# Var_7_scheme.net
KiCad netlist of a schematic drawn in Altium Designer
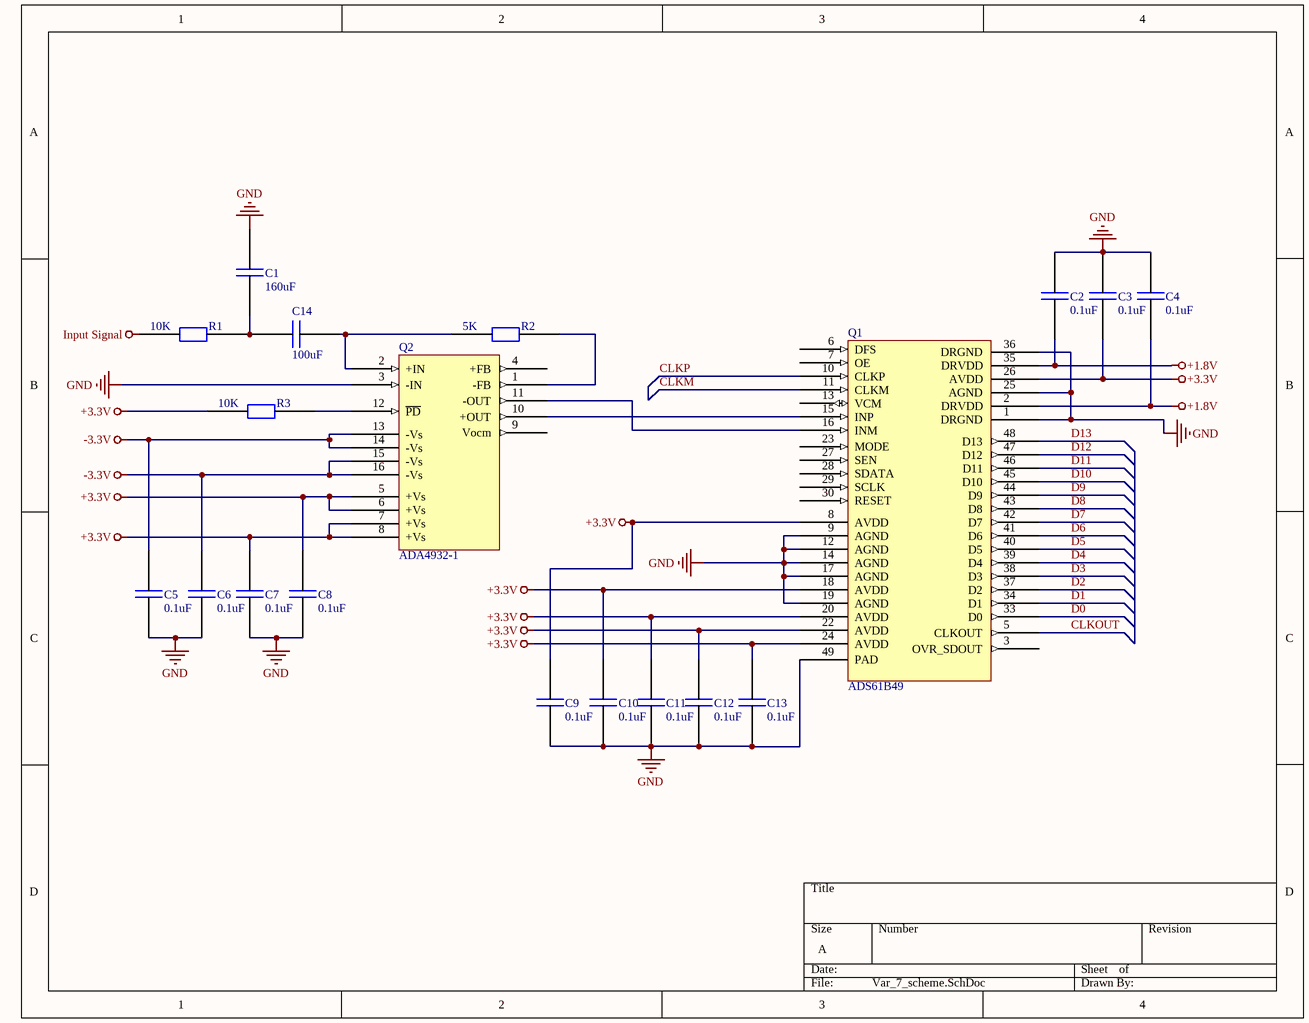
[diagram p0: Var_7_scheme.SchDoc]

(export (version "E")
  (design (tool "Eeschema 10.0.6"))
  (components
    (comp (ref "C1") (value "160uF") (footprint "CAP0603") (libsource (lib "Var_7") (part "Capacitor")))
    (comp (ref "C2") (value "0.1uF") (footprint "CAP0603") (libsource (lib "Var_7") (part "Capacitor")))
    (comp (ref "C3") (value "0.1uF") (footprint "CAP0603") (libsource (lib "Var_7") (part "Capacitor")))
    (comp (ref "C4") (value "0.1uF") (footprint "CAP0603") (libsource (lib "Var_7") (part "Capacitor")))
    (comp (ref "C5") (value "0.1uF") (footprint "CAP0603") (libsource (lib "Var_7") (part "Capacitor")))
    (comp (ref "C6") (value "0.1uF") (footprint "CAP0603") (libsource (lib "Var_7") (part "Capacitor")))
    (comp (ref "C7") (value "0.1uF") (footprint "CAP0603") (libsource (lib "Var_7") (part "Capacitor")))
    (comp (ref "C8") (value "0.1uF") (footprint "CAP0603") (libsource (lib "Var_7") (part "Capacitor")))
    (comp (ref "C9") (value "0.1uF") (footprint "CAP0603") (libsource (lib "Var_7") (part "Capacitor")))
    (comp (ref "C10") (value "0.1uF") (footprint "CAP0603") (libsource (lib "Var_7") (part "Capacitor")))
    (comp (ref "C11") (value "0.1uF") (footprint "CAP0603") (libsource (lib "Var_7") (part "Capacitor")))
    (comp (ref "C12") (value "0.1uF") (footprint "CAP0603") (libsource (lib "Var_7") (part "Capacitor")))
    (comp (ref "C13") (value "0.1uF") (footprint "CAP0603") (libsource (lib "Var_7") (part "Capacitor")))
    (comp (ref "C14") (value "100uF") (footprint "CAP0603") (libsource (lib "Var_7") (part "Capacitor")))
    (comp (ref "Q1") (value "ADS61B49") (footprint "QFN49") (libsource (lib "Var_7") (part "ADS61B49")))
    (comp (ref "Q2") (value "ADA4932-1") (footprint "QFN17") (libsource (lib "Var_7") (part "ADA4932-1")))
    (comp (ref "R1") (value "10K") (footprint "RES0805") (libsource (lib "Var_7") (part "Resistor")))
    (comp (ref "R2") (value "5K") (footprint "RES0805") (libsource (lib "Var_7") (part "Resistor")))
    (comp (ref "R3") (value "10K") (footprint "RES0805") (libsource (lib "Var_7") (part "Resistor")))
  )
  (nets
    (net (code "1") (name "+1.8V") (class "Default")
      (node (ref "C2") (pin "2") (pinfunction "2_2") (pintype "passive"))
      (node (ref "C4") (pin "2") (pinfunction "2_2") (pintype "passive"))
      (node (ref "Q1") (pin "2") (pinfunction "DRVDD_2") (pintype "power_in"))
      (node (ref "Q1") (pin "35") (pinfunction "DRVDD_35") (pintype "power_in"))
    )
    (net (code "2") (name "+3.3V") (class "Default")
      (node (ref "C10") (pin "1") (pinfunction "1_1") (pintype "passive"))
      (node (ref "C11") (pin "1") (pinfunction "1_1") (pintype "passive"))
      (node (ref "C12") (pin "1") (pinfunction "1_1") (pintype "passive"))
      (node (ref "C13") (pin "1") (pinfunction "1_1") (pintype "passive"))
      (node (ref "C3") (pin "2") (pinfunction "2_2") (pintype "passive"))
      (node (ref "C7") (pin "1") (pinfunction "1_1") (pintype "passive"))
      (node (ref "C8") (pin "1") (pinfunction "1_1") (pintype "passive"))
      (node (ref "C9") (pin "1") (pinfunction "1_1") (pintype "passive"))
      (node (ref "Q1") (pin "18") (pinfunction "AVDD_18") (pintype "power_in"))
      (node (ref "Q1") (pin "20") (pinfunction "AVDD_20") (pintype "power_in"))
      (node (ref "Q1") (pin "22") (pinfunction "AVDD_22") (pintype "power_in"))
      (node (ref "Q1") (pin "24") (pinfunction "AVDD_24") (pintype "power_in"))
      (node (ref "Q1") (pin "26") (pinfunction "AVDD_26") (pintype "power_in"))
      (node (ref "Q1") (pin "8") (pinfunction "AVDD_8") (pintype "power_in"))
      (node (ref "Q2") (pin "5") (pinfunction "+Vs_5") (pintype "power_in"))
      (node (ref "Q2") (pin "6") (pinfunction "+Vs_6") (pintype "power_in"))
      (node (ref "Q2") (pin "7") (pinfunction "+Vs_7") (pintype "power_in"))
      (node (ref "Q2") (pin "8") (pinfunction "+Vs_8") (pintype "power_in"))
      (node (ref "R3") (pin "2") (pinfunction "2_2") (pintype "passive"))
    )
    (net (code "3") (name "-3.3V") (class "Default")
      (node (ref "C5") (pin "1") (pinfunction "1_1") (pintype "passive"))
      (node (ref "C6") (pin "1") (pinfunction "1_1") (pintype "passive"))
      (node (ref "Q2") (pin "13") (pinfunction "-Vs_13") (pintype "power_in"))
      (node (ref "Q2") (pin "14") (pinfunction "-Vs_14") (pintype "power_in"))
      (node (ref "Q2") (pin "15") (pinfunction "-Vs_15") (pintype "power_in"))
      (node (ref "Q2") (pin "16") (pinfunction "-Vs_16") (pintype "power_in"))
    )
    (net (code "4") (name "/CLKM") (class "Default")
      (node (ref "Q1") (pin "11") (pinfunction "CLKM_11") (pintype "input"))
    )
    (net (code "5") (name "/CLKOUT") (class "Default")
      (node (ref "Q1") (pin "5") (pinfunction "CLKOUT_5") (pintype "output"))
    )
    (net (code "6") (name "/CLKP") (class "Default")
      (node (ref "Q1") (pin "10") (pinfunction "CLKP_10") (pintype "input"))
    )
    (net (code "7") (name "/D0") (class "Default")
      (node (ref "Q1") (pin "33") (pinfunction "D0_33") (pintype "output"))
    )
    (net (code "8") (name "/D1") (class "Default")
      (node (ref "Q1") (pin "34") (pinfunction "D1_34") (pintype "output"))
    )
    (net (code "9") (name "/D2") (class "Default")
      (node (ref "Q1") (pin "37") (pinfunction "D2_37") (pintype "output"))
    )
    (net (code "10") (name "/D3") (class "Default")
      (node (ref "Q1") (pin "38") (pinfunction "D3_38") (pintype "output"))
    )
    (net (code "11") (name "/D4") (class "Default")
      (node (ref "Q1") (pin "39") (pinfunction "D4_39") (pintype "output"))
    )
    (net (code "12") (name "/D5") (class "Default")
      (node (ref "Q1") (pin "40") (pinfunction "D5_40") (pintype "output"))
    )
    (net (code "13") (name "/D6") (class "Default")
      (node (ref "Q1") (pin "41") (pinfunction "D6_41") (pintype "output"))
    )
    (net (code "14") (name "/D7") (class "Default")
      (node (ref "Q1") (pin "42") (pinfunction "D7_42") (pintype "output"))
    )
    (net (code "15") (name "/D8") (class "Default")
      (node (ref "Q1") (pin "43") (pinfunction "D8_43") (pintype "output"))
    )
    (net (code "16") (name "/D9") (class "Default")
      (node (ref "Q1") (pin "44") (pinfunction "D9_44") (pintype "output"))
    )
    (net (code "17") (name "/D10") (class "Default")
      (node (ref "Q1") (pin "45") (pinfunction "D10_45") (pintype "output"))
    )
    (net (code "18") (name "/D11") (class "Default")
      (node (ref "Q1") (pin "46") (pinfunction "D11_46") (pintype "output"))
    )
    (net (code "19") (name "/D12") (class "Default")
      (node (ref "Q1") (pin "47") (pinfunction "D12_47") (pintype "output"))
    )
    (net (code "20") (name "/D13") (class "Default")
      (node (ref "Q1") (pin "48") (pinfunction "D13_48") (pintype "output"))
    )
    (net (code "21") (name "GND") (class "Default")
      (node (ref "C1") (pin "2") (pinfunction "2_2") (pintype "passive"))
      (node (ref "C10") (pin "2") (pinfunction "2_2") (pintype "passive"))
      (node (ref "C11") (pin "2") (pinfunction "2_2") (pintype "passive"))
      (node (ref "C12") (pin "2") (pinfunction "2_2") (pintype "passive"))
      (node (ref "C13") (pin "2") (pinfunction "2_2") (pintype "passive"))
      (node (ref "C2") (pin "1") (pinfunction "1_1") (pintype "passive"))
      (node (ref "C3") (pin "1") (pinfunction "1_1") (pintype "passive"))
      (node (ref "C4") (pin "1") (pinfunction "1_1") (pintype "passive"))
      (node (ref "C5") (pin "2") (pinfunction "2_2") (pintype "passive"))
      (node (ref "C6") (pin "2") (pinfunction "2_2") (pintype "passive"))
      (node (ref "C7") (pin "2") (pinfunction "2_2") (pintype "passive"))
      (node (ref "C8") (pin "2") (pinfunction "2_2") (pintype "passive"))
      (node (ref "C9") (pin "2") (pinfunction "2_2") (pintype "passive"))
      (node (ref "Q1") (pin "1") (pinfunction "DRGND_1") (pintype "power_in"))
      (node (ref "Q1") (pin "12") (pinfunction "AGND_12") (pintype "power_in"))
      (node (ref "Q1") (pin "14") (pinfunction "AGND_14") (pintype "power_in"))
      (node (ref "Q1") (pin "17") (pinfunction "AGND_17") (pintype "power_in"))
      (node (ref "Q1") (pin "19") (pinfunction "AGND_19") (pintype "power_in"))
      (node (ref "Q1") (pin "25") (pinfunction "AGND_25") (pintype "power_in"))
      (node (ref "Q1") (pin "36") (pinfunction "DRGND_36") (pintype "power_in"))
      (node (ref "Q1") (pin "49") (pinfunction "PAD_49") (pintype "passive"))
      (node (ref "Q1") (pin "9") (pinfunction "AGND_9") (pintype "power_in"))
      (node (ref "Q2") (pin "3") (pinfunction "-IN_3") (pintype "input"))
    )
    (net (code "22") (name "Input Signal") (class "Default")
      (node (ref "R1") (pin "2") (pinfunction "2_2") (pintype "passive"))
    )
    (net (code "23") (name "Net-(C1-Pad1)") (class "Default")
      (node (ref "C1") (pin "1") (pinfunction "1_1") (pintype "passive"))
      (node (ref "C14") (pin "1") (pinfunction "1_1") (pintype "passive"))
      (node (ref "R1") (pin "1") (pinfunction "1_1") (pintype "passive"))
    )
    (net (code "24") (name "Net-(Q1-INM)") (class "Default")
      (node (ref "Q1") (pin "16") (pinfunction "INM_16") (pintype "input"))
      (node (ref "Q2") (pin "11") (pinfunction "-OUT_11") (pintype "output"))
    )
    (net (code "25") (name "Net-(Q1-INP)") (class "Default")
      (node (ref "Q1") (pin "15") (pinfunction "INP_15") (pintype "input"))
      (node (ref "Q2") (pin "10") (pinfunction "+OUT_10") (pintype "output"))
    )
    (net (code "26") (name "Net-(Q2-+IN)") (class "Default")
      (node (ref "C14") (pin "2") (pinfunction "2_2") (pintype "passive"))
      (node (ref "Q2") (pin "2") (pinfunction "+IN_2") (pintype "input"))
      (node (ref "R2") (pin "2") (pinfunction "2_2") (pintype "passive"))
    )
    (net (code "27") (name "Net-(Q2--FB)") (class "Default")
      (node (ref "Q2") (pin "1") (pinfunction "-FB_1") (pintype "output"))
      (node (ref "R2") (pin "1") (pinfunction "1_1") (pintype "passive"))
    )
    (net (code "28") (name "Net-(Q2-~{PD})") (class "Default")
      (node (ref "Q2") (pin "12") (pinfunction "~{PD}_12") (pintype "input"))
      (node (ref "R3") (pin "1") (pinfunction "1_1") (pintype "passive"))
    )
    (net (code "29") (name "unconnected-(Q1-DFS-Pad6)") (class "Default")
      (node (ref "Q1") (pin "6") (pinfunction "DFS_6") (pintype "input"))
    )
    (net (code "30") (name "unconnected-(Q1-MODE-Pad23)") (class "Default")
      (node (ref "Q1") (pin "23") (pinfunction "MODE_23") (pintype "input"))
    )
    (net (code "31") (name "unconnected-(Q1-NC-Pad21)") (class "Default")
      (node (ref "Q1") (pin "21") (pinfunction "NC_21") (pintype "passive"))
    )
    (net (code "32") (name "unconnected-(Q1-NC-Pad31)") (class "Default")
      (node (ref "Q1") (pin "31") (pinfunction "NC_31") (pintype "passive"))
    )
    (net (code "33") (name "unconnected-(Q1-NC-Pad32)") (class "Default")
      (node (ref "Q1") (pin "32") (pinfunction "NC_32") (pintype "passive"))
    )
    (net (code "34") (name "unconnected-(Q1-OE-Pad7)") (class "Default")
      (node (ref "Q1") (pin "7") (pinfunction "OE_7") (pintype "input"))
    )
    (net (code "35") (name "unconnected-(Q1-OVR_SDOUT-Pad3)") (class "Default")
      (node (ref "Q1") (pin "3") (pinfunction "OVR_SDOUT_3") (pintype "output"))
    )
    (net (code "36") (name "unconnected-(Q1-RESET-Pad30)") (class "Default")
      (node (ref "Q1") (pin "30") (pinfunction "RESET_30") (pintype "input"))
    )
    (net (code "37") (name "unconnected-(Q1-SCLK-Pad29)") (class "Default")
      (node (ref "Q1") (pin "29") (pinfunction "SCLK_29") (pintype "input"))
    )
    (net (code "38") (name "unconnected-(Q1-SDATA-Pad28)") (class "Default")
      (node (ref "Q1") (pin "28") (pinfunction "SDATA_28") (pintype "input"))
    )
    (net (code "39") (name "unconnected-(Q1-SEN-Pad27)") (class "Default")
      (node (ref "Q1") (pin "27") (pinfunction "SEN_27") (pintype "input"))
    )
    (net (code "40") (name "unconnected-(Q1-UNUSED-Pad4)") (class "Default")
      (node (ref "Q1") (pin "4") (pinfunction "UNUSED_4") (pintype "passive"))
    )
    (net (code "41") (name "unconnected-(Q1-VCM-Pad13)") (class "Default")
      (node (ref "Q1") (pin "13") (pinfunction "VCM_13") (pintype "bidirectional"))
    )
    (net (code "42") (name "unconnected-(Q2-+FB-Pad4)") (class "Default")
      (node (ref "Q2") (pin "4") (pinfunction "+FB_4") (pintype "output"))
    )
    (net (code "43") (name "unconnected-(Q2-PAD-Pad17)") (class "Default")
      (node (ref "Q2") (pin "17") (pinfunction "PAD_17") (pintype "passive"))
    )
    (net (code "44") (name "unconnected-(Q2-Vocm-Pad9)") (class "Default")
      (node (ref "Q2") (pin "9") (pinfunction "Vocm_9") (pintype "output"))
    )
  )
)
